# Connector_Exp.net
KiCad netlist of a schematic drawn in Altium Designer
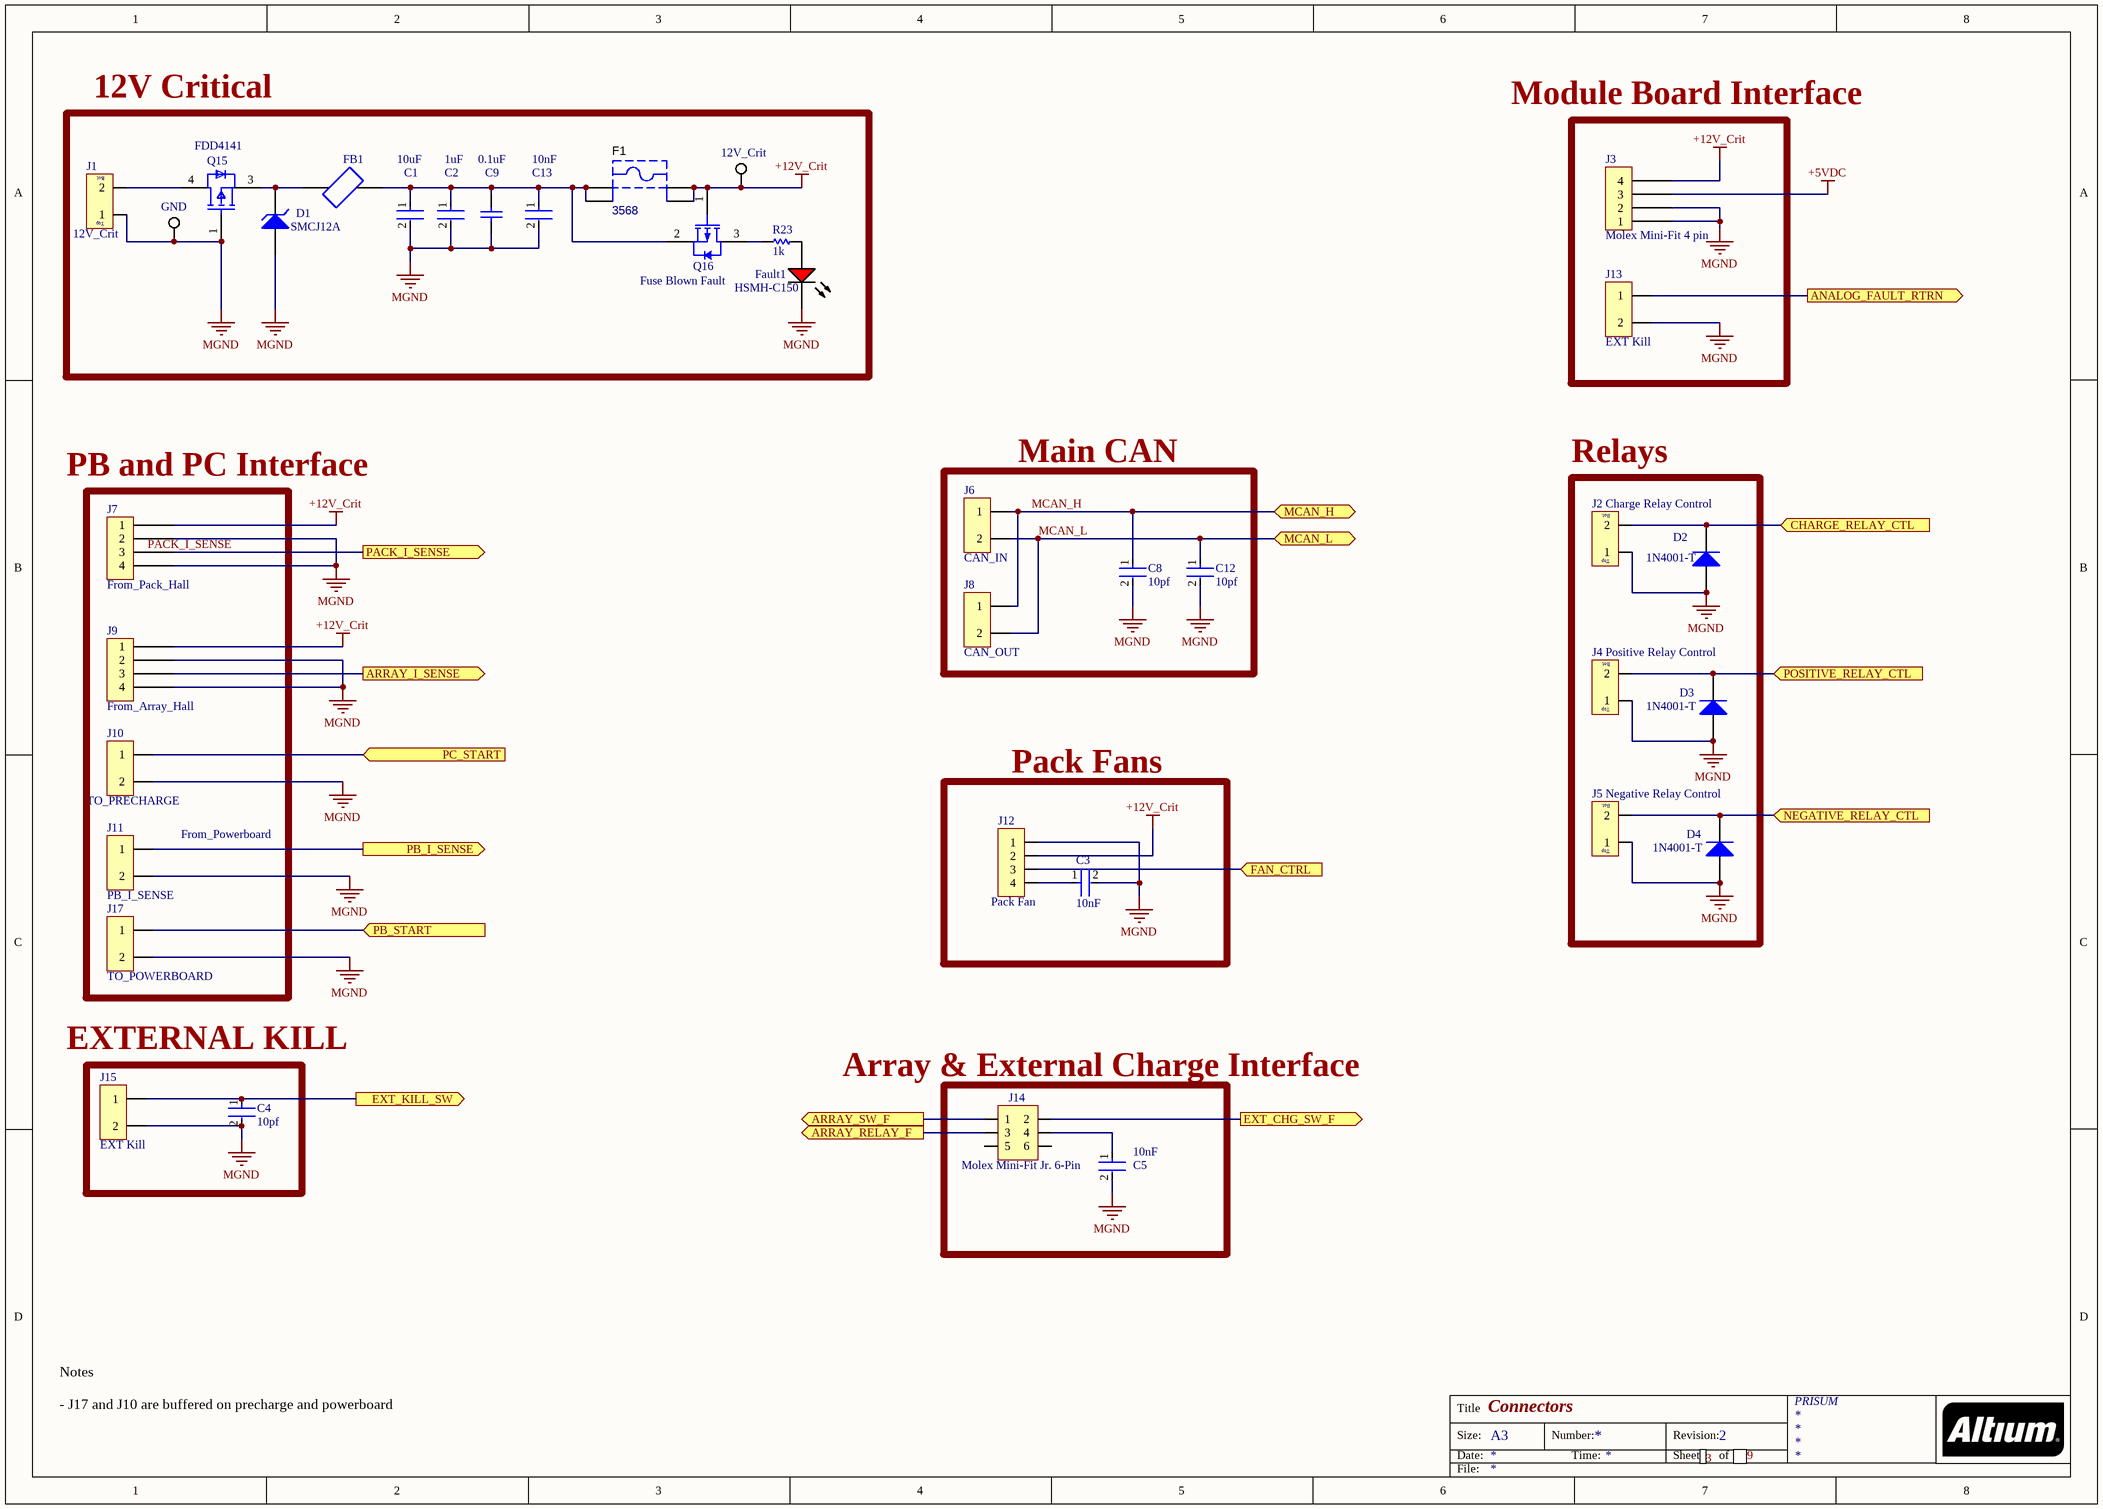
[diagram p0: Connector_Exp.SchDoc]

(export (version "E")
  (design (tool "Eeschema 10.0.6"))
  (components
    (comp (ref "12V_Crit")
      (value "Test Point")
      (footprint "Test Point")
      (libsource (lib "BPS") (part "Test Point"))
    )
    (comp (ref "C1")
      (value "CL31A106MOHNNNE")
      (footprint "FP-CL31-IPC_A")
      (description "Cap Ceramic 10uF 16V X5R ±20% SMD 1206 +85°C Embossed T/R")
      (fields (field (name "CAPACITANCE") "10uF") (field (name "TOLERANCE") "20%"))
      (libsource (lib "Altium Content Vault") (part "b4654b650e69147ec39a6b967a45e02"))
    )
    (comp (ref "C2")
      (value "CL31F105ZOCNNNC")
      (footprint "FP-CL31-IPC_A")
      (description "Cap Ceramic 1uF 16V Y5V -20/+80% SMD 1206 +85°C Embossed T/R")
      (fields (field (name "TOLERANCE") "80%") (field (name "CAPACITANCE") "1uF"))
      (libsource (lib "Altium Content Vault") (part "b4654b650e69147ec39a6b967a45e02"))
    )
    (comp (ref "C3")
      (value "CGA3E2X8R2A103K080AD")
      (footprint "FP-CGA3E-0_3-0_1-IPC_A")
      (description "Cap Ceramic 10nF 100V X8R 10% Pad SMD 0603 +150°C Automotive T/R")
      (fields (field (name "CAPACITANCE") "10nF") (field (name "TOLERANCE") "10%"))
      (libsource (lib "Altium Content Vault") (part "b4654b650e69147ec39a6b967a45e02"))
    )
    (comp (ref "C4")
      (value "10pf")
      (footprint "FP-C0805C-DN-MFG")
      (description "C0805 10 pF C0G 30ppm/°C 2.00% 50 V")
      (fields
        (field (name "TOLERANCE") "0.02")
        (field (name "OCTOPART") "https://octopart.com/c0805c100g5gactu-kemet-20071675")
      )
      (libsource (lib "Altium Content Vault") (part "b4654b650e69147ec39a6b967a45e02"))
    )
    (comp (ref "C5")
      (value "CGA3E2X8R2A103K080AD")
      (footprint "FP-CGA3E-0_3-0_1-IPC_A")
      (description "Cap Ceramic 10nF 100V X8R 10% Pad SMD 0603 +150°C Automotive T/R")
      (fields (field (name "CAPACITANCE") "10nF") (field (name "TOLERANCE") "10%"))
      (libsource (lib "Altium Content Vault") (part "b4654b650e69147ec39a6b967a45e02"))
    )
    (comp (ref "C8")
      (value "10pf")
      (footprint "FP-C0805C-DN-MFG")
      (description "C0805 10 pF C0G 30ppm/°C 2.00% 50 V")
      (fields
        (field (name "TOLERANCE") "0.02")
        (field (name "OCTOPART") "https://octopart.com/c0805c100g5gactu-kemet-20071675")
      )
      (libsource (lib "Altium Content Vault") (part "b4654b650e69147ec39a6b967a45e02"))
    )
    (comp (ref "C9")
      (value "08055C104JAT2A")
      (footprint "CAPC2013X94X50LL20T25")
      (description "Chip Capacitor, 0.1 uF, +/- 5%, 50 V, -55 to 125 degC, 0805 (2012 Metric), RoHS, Tape and Reel")
      (fields
        (field (name "CAPACITANCE") "0.1uF")
        (field (name "TOLERANCE") "5%")
        (field (name "MANUFACTURER") "AVX")
      )
      (libsource (lib "Altium Content Vault") (part "CAP-NP-2"))
    )
    (comp (ref "C12")
      (value "10pf")
      (footprint "FP-C0805C-DN-MFG")
      (description "C0805 10 pF C0G 30ppm/°C 2.00% 50 V")
      (fields
        (field (name "TOLERANCE") "0.02")
        (field (name "OCTOPART") "https://octopart.com/c0805c100g5gactu-kemet-20071675")
      )
      (libsource (lib "Altium Content Vault") (part "b4654b650e69147ec39a6b967a45e02"))
    )
    (comp (ref "C13")
      (value "CGA3E2X8R2A103K080AD")
      (footprint "FP-CGA3E-0_3-0_1-IPC_A")
      (description "Cap Ceramic 10nF 100V X8R 10% Pad SMD 0603 +150°C Automotive T/R")
      (fields (field (name "CAPACITANCE") "10nF") (field (name "TOLERANCE") "10%"))
      (libsource (lib "Altium Content Vault") (part "b4654b650e69147ec39a6b967a45e02"))
    )
    (comp (ref "D1")
      (value "SMCJ12A")
      (footprint "LFUS-DO-214AB-2_V")
      (fields (field (name "MANUFACTURER") "Littelfuse"))
      (libsource (lib "Altium Content Vault") (part "DZEN-AK-2"))
    )
    (comp (ref "D2")
      (value "1N4001-T")
      (footprint "DIOD-DO-41-P-2_V")
      (description "1.0 A Rectifier, 15 pF, 50 V, -65 to 150 degC, 2-Pin DO-41 Plastic, RoHS, Tape and Reel")
      (fields (field (name "MANUFACTURER") "Diodes Inc"))
      (libsource (lib "Altium Content Vault") (part "DIOD-D-A1K2-2"))
    )
    (comp (ref "D3")
      (value "1N4001-T")
      (footprint "DIOD-DO-41-P-2_V")
      (description "1.0 A Rectifier, 15 pF, 50 V, -65 to 150 degC, 2-Pin DO-41 Plastic, RoHS, Tape and Reel")
      (fields (field (name "MANUFACTURER") "Diodes Inc"))
      (libsource (lib "Altium Content Vault") (part "DIOD-D-A1K2-2"))
    )
    (comp (ref "D4")
      (value "1N4001-T")
      (footprint "DIOD-DO-41-P-2_V")
      (description "1.0 A Rectifier, 15 pF, 50 V, -65 to 150 degC, 2-Pin DO-41 Plastic, RoHS, Tape and Reel")
      (fields (field (name "MANUFACTURER") "Diodes Inc"))
      (libsource (lib "Altium Content Vault") (part "DIOD-D-A1K2-2"))
    )
    (comp (ref "F1")
      (value "3568")
      (footprint "KSTN-3568_V")
      (description "Fuse Holder, 20 A, 500 V, -50 to 145 degC, 4-Pin THD, RoHS")
      (fields (field (name "MANUFACTURER") "Keystone"))
      (libsource (lib "Altium Content Vault") (part "FUSE_HOLDER-4"))
    )
    (comp (ref "Fault1")
      (value "HSMH-C150")
      (footprint "AVAG-HSMX-C150_V")
      (description "LED Uni-Color Red, 65 mW, 25 mA, -40 to 85 degC, 2-Pin SMD, RoHS, Tape and Reel")
      (fields (field (name "MANUFACTURER") "Avago"))
      (libsource (lib "Altium Content Vault") (part "LED-RED-AK-2"))
    )
    (comp (ref "FB1")
      (value "HI1206N800R-10")
      (footprint "FB_HI1206N800R-10")
      (description "80 Ohms @ 100MHz 1 Power, Signal Line Ferrite Bead 1206 (3216 Metric) 3A 35mOhm")
      (fields
        (field (name "MF") "Laird-Signal Integrity")
        (field (name "DIGI-KEY_PART_NUMBER") "240-2409-1-ND")
      )
      (libsource (lib "BPS") (part "HI1206N800R-10"))
    )
    (comp (ref "GND")
      (value "Test Point")
      (footprint "Test Point")
      (libsource (lib "BPS") (part "Test Point"))
    )
    (comp (ref "J1")
      (value "12V_Crit")
      (footprint "CONN_2P_MEGAFIT_HORIZONTAL")
      (fields
        (field (name "MANUFACTURER PART NUMBER") "0768250002")
        (field (name "MANUFACTURER") "Molex")
        (field (name "DIGIKEY PART NUMBER") "WM11969-ND")
      )
      (libsource (lib "Connectors (1)") (part "CONN_2P_MEGAFIT_HORIZONTAL"))
    )
    (comp (ref "J2")
      (value "Charge Relay Control")
      (footprint "CONN_2P_MEGAFIT_HORIZONTAL")
      (fields
        (field (name "MANUFACTURER PART NUMBER") "0768250002")
        (field (name "MANUFACTURER") "Molex")
        (field (name "DIGIKEY PART NUMBER") "WM11969-ND")
      )
      (libsource (lib "Connectors (1)") (part "CONN_2P_MEGAFIT_HORIZONTAL"))
    )
    (comp (ref "J3")
      (value "Molex Mini-Fit 4 pin")
      (footprint "Molex Mini-Fit Jr. 4-Pin - no flange")
      (libsource (lib "") (part "Molex Mini-Fit 4 pin_1"))
    )
    (comp (ref "J4")
      (value "Positive Relay Control")
      (footprint "CONN_2P_MEGAFIT_HORIZONTAL")
      (fields
        (field (name "MANUFACTURER PART NUMBER") "0768250002")
        (field (name "MANUFACTURER") "Molex")
        (field (name "DIGIKEY PART NUMBER") "WM11969-ND")
      )
      (libsource (lib "Connectors (1)") (part "CONN_2P_MEGAFIT_HORIZONTAL"))
    )
    (comp (ref "J5")
      (value "Negative Relay Control")
      (footprint "CONN_2P_MEGAFIT_HORIZONTAL")
      (fields
        (field (name "MANUFACTURER PART NUMBER") "0768250002")
        (field (name "MANUFACTURER") "Molex")
        (field (name "DIGIKEY PART NUMBER") "WM11969-ND")
      )
      (libsource (lib "Connectors (1)") (part "CONN_2P_MEGAFIT_HORIZONTAL"))
    )
    (comp (ref "J6")
      (value "CAN_IN")
      (footprint "Mini-Fit Jr. 2")
      (description "Mini-Fit Jr. 2-pin Right Angle")
      (fields
        (field (name "MANUFACTURER") "Molex Inc")
        (field (name "MANUFACTURER PART NUMBER") "0039300020")
      )
      (libsource (lib "BPSHeadNode") (part "Mini-Fit Jr. 2-pin"))
    )
    (comp (ref "J7")
      (value "From_Pack_Hall")
      (footprint "Molex Mini-Fit Jr. 4-Pin - no flange")
      (libsource (lib "BPS") (part "Molex Mini-Fit 4 pin"))
    )
    (comp (ref "J8")
      (value "CAN_OUT")
      (footprint "Mini-Fit Jr. 2")
      (description "Mini-Fit Jr. 2-pin Right Angle")
      (fields
        (field (name "MANUFACTURER") "Molex Inc")
        (field (name "MANUFACTURER PART NUMBER") "0039300020")
      )
      (libsource (lib "BPSHeadNode") (part "Mini-Fit Jr. 2-pin"))
    )
    (comp (ref "J9")
      (value "From_Array_Hall")
      (footprint "Molex Mini-Fit Jr. 4-Pin - no flange")
      (libsource (lib "BPS") (part "Molex Mini-Fit 4 pin"))
    )
    (comp (ref "J10")
      (value "TO_PRECHARGE")
      (footprint "Mini-Fit Jr. 2")
      (description "Mini-Fit Jr. 2-pin Right Angle")
      (fields
        (field (name "MANUFACTURER") "Molex Inc")
        (field (name "MANUFACTURER PART NUMBER") "0039300020")
      )
      (libsource (lib "BPSHeadNode") (part "Mini-Fit Jr. 2-pin"))
    )
    (comp (ref "J11")
      (value "PB_I_SENSE")
      (footprint "Mini-Fit Jr. 2")
      (description "Mini-Fit Jr. 2-pin Right Angle")
      (fields
        (field (name "MANUFACTURER") "Molex Inc")
        (field (name "MANUFACTURER PART NUMBER") "0039300020")
      )
      (libsource (lib "BPSHeadNode") (part "Mini-Fit Jr. 2-pin"))
    )
    (comp (ref "J12")
      (value "Molex Mini-Fit Jr. 4-Pin no flange")
      (footprint "Molex Mini-Fit Jr. 4-Pin - no flange")
      (description "4-Pin Molex Mini-Fit Jr. Header")
      (fields
        (field (name "MANUFACTURER") "Molex")
        (field (name "MANUFACTURER PART NUMBER") "0039301040")
        (field (name "DRAWN BY") "Aaron Mills")
      )
      (libsource (lib "BPSHeadNode") (part "Molex Mini-Fit Jr. 4-Pin"))
    )
    (comp (ref "J13")
      (value "EXT Kill")
      (footprint "Mini-Fit Jr. 2")
      (description "Mini-Fit Jr. 2-pin Right Angle")
      (fields
        (field (name "MANUFACTURER") "Molex Inc")
        (field (name "MANUFACTURER PART NUMBER") "0039300020")
      )
      (libsource (lib "BPSHeadNode") (part "Mini-Fit Jr. 2-pin"))
    )
    (comp (ref "J14")
      (value "Molex Mini-Fit Jr. 6-Pin")
      (footprint "Molex Mini-Fit Jr. 6-Pin")
      (description "6-Pin Molex Mini-Fit Jr. Header  through hole")
      (fields (field (name "MANUFACTURER") "Molex") (field (name "DRAWN BY") "Aaron Mills"))
      (libsource (lib "BPSHeadNode") (part "Molex Mini-Fit Jr. 6-Pin"))
    )
    (comp (ref "J15")
      (value "EXT Kill")
      (footprint "Mini-Fit Jr. 2")
      (description "Mini-Fit Jr. 2-pin Right Angle")
      (fields
        (field (name "MANUFACTURER") "Molex Inc")
        (field (name "MANUFACTURER PART NUMBER") "0039300020")
      )
      (libsource (lib "BPSHeadNode") (part "Mini-Fit Jr. 2-pin"))
    )
    (comp (ref "J17")
      (value "TO_POWERBOARD")
      (footprint "Mini-Fit Jr. 2")
      (description "Mini-Fit Jr. 2-pin Right Angle")
      (fields
        (field (name "MANUFACTURER") "Molex Inc")
        (field (name "MANUFACTURER PART NUMBER") "0039300020")
      )
      (libsource (lib "BPSHeadNode") (part "Mini-Fit Jr. 2-pin"))
    )
    (comp (ref "Q15")
      (value "FDD4141")
      (footprint "FP-369AS-MFG")
      (description "MOSFET P-CH 40V 10.8A DPAK")
      (fields
        (field (name "OCTOPART") "https://octopart.com/fdd4141-on+semiconductor-84325802")
        (field (name "MANUFACTURER") "ON Semiconductor")
      )
      (libsource (lib "Altium Content Vault") (part "ec195c925100855187fe8c06440c3e1"))
    )
    (comp (ref "Q16")
      (value "Fuse Blown Fault")
      (footprint "INTR-SOT-23-3_V")
      (fields (field (name "MANUFACTURER") "International Rectifier"))
      (libsource (lib "Altium Content Vault") (part "PEMOS-GSD-3"))
    )
    (comp (ref "R23")
      (value "RES_1k_1%_0603")
      (footprint "R_0603")
      (fields
        (field (name "MANUFACTURER PART NUMBER") "RC0603FR-071KL")
        (field (name "MANUFACTURER") "Yageo")
        (field (name "DIGIKEY PART NUMBER") "311-1.00KHRCT-ND")
        (field (name "SCHEMATICINFORMATION") "1k")
      )
      (libsource (lib "Resistors") (part "RES_1k_1%_0603"))
    )
  )
  (nets
    (net (code "1") (name "+5VDC") (class "Default")
      (node (ref "J3") (pin "3") (pinfunction "3_3") (pintype "passive"))
    )
    (net (code "2") (name "+12V_Crit") (class "Default")
      (node (ref "12V_Crit") (pin "1") (pinfunction "1_1") (pintype "passive"))
      (node (ref "F1") (pin "3") (pinfunction "3_3") (pintype "passive"))
      (node (ref "F1") (pin "4") (pinfunction "4_4") (pintype "passive"))
      (node (ref "J12") (pin "2") (pinfunction "2_2") (pintype "passive"))
      (node (ref "J3") (pin "4") (pinfunction "4_4") (pintype "passive"))
      (node (ref "J7") (pin "1") (pinfunction "1_1") (pintype "passive"))
      (node (ref "J9") (pin "1") (pinfunction "1_1") (pintype "passive"))
      (node (ref "Q16") (pin "1") (pinfunction "GATE_1") (pintype "passive"))
    )
    (net (code "3") (name "/ANALOG_FAULT_RTRN") (class "Default")
      (node (ref "J13") (pin "1") (pinfunction "1_1") (pintype "passive"))
    )
    (net (code "4") (name "/ARRAY_I_SENSE") (class "Default")
      (node (ref "J9") (pin "3") (pinfunction "3_3") (pintype "passive"))
    )
    (net (code "5") (name "/ARRAY_RELAY_F") (class "Default")
      (node (ref "J14") (pin "3") (pinfunction "3_3") (pintype "passive"))
    )
    (net (code "6") (name "/ARRAY_SW_F") (class "Default")
      (node (ref "J14") (pin "1") (pinfunction "1_1") (pintype "passive"))
    )
    (net (code "7") (name "/CHARGE_RELAY_CTL") (class "Default")
      (node (ref "D2") (pin "2") (pinfunction "K_2") (pintype "passive"))
      (node (ref "J2") (pin "2") (pinfunction "2_2") (pintype "passive"))
    )
    (net (code "8") (name "/EXT_CHG_SW_F") (class "Default")
      (node (ref "J14") (pin "2") (pinfunction "2_2") (pintype "passive"))
    )
    (net (code "9") (name "/EXT_KILL_SW") (class "Default")
      (node (ref "C4") (pin "1") (pinfunction "1_1") (pintype "passive"))
      (node (ref "J15") (pin "1") (pinfunction "1_1") (pintype "passive"))
    )
    (net (code "10") (name "/FAN_CTRL") (class "Default")
      (node (ref "J12") (pin "3") (pinfunction "3_3") (pintype "passive"))
    )
    (net (code "11") (name "/MCAN_H") (class "Default")
      (node (ref "C8") (pin "1") (pinfunction "1_1") (pintype "passive"))
      (node (ref "J6") (pin "1") (pinfunction "1_1") (pintype "passive"))
      (node (ref "J8") (pin "1") (pinfunction "1_1") (pintype "passive"))
    )
    (net (code "12") (name "/MCAN_L") (class "Default")
      (node (ref "C12") (pin "1") (pinfunction "1_1") (pintype "passive"))
      (node (ref "J6") (pin "2") (pinfunction "2_2") (pintype "passive"))
      (node (ref "J8") (pin "2") (pinfunction "2_2") (pintype "passive"))
    )
    (net (code "13") (name "/NEGATIVE_RELAY_CTL") (class "Default")
      (node (ref "D4") (pin "2") (pinfunction "K_2") (pintype "passive"))
      (node (ref "J5") (pin "2") (pinfunction "2_2") (pintype "passive"))
    )
    (net (code "14") (name "/PACK_I_SENSE") (class "Default")
      (node (ref "J7") (pin "3") (pinfunction "3_3") (pintype "passive"))
    )
    (net (code "15") (name "/PB_I_SENSE") (class "Default")
      (node (ref "J11") (pin "1") (pinfunction "1_1") (pintype "passive"))
    )
    (net (code "16") (name "/PB_START") (class "Default")
      (node (ref "J17") (pin "1") (pinfunction "1_1") (pintype "passive"))
    )
    (net (code "17") (name "/PC_START") (class "Default")
      (node (ref "J10") (pin "1") (pinfunction "1_1") (pintype "passive"))
    )
    (net (code "18") (name "/POSITIVE_RELAY_CTL") (class "Default")
      (node (ref "D3") (pin "2") (pinfunction "K_2") (pintype "passive"))
      (node (ref "J4") (pin "2") (pinfunction "2_2") (pintype "passive"))
    )
    (net (code "19") (name "MGND") (class "Default")
      (node (ref "C1") (pin "2") (pinfunction "2_2") (pintype "passive"))
      (node (ref "C12") (pin "2") (pinfunction "2_2") (pintype "passive"))
      (node (ref "C13") (pin "2") (pinfunction "2_2") (pintype "passive"))
      (node (ref "C2") (pin "2") (pinfunction "2_2") (pintype "passive"))
      (node (ref "C3") (pin "2") (pinfunction "2_2") (pintype "passive"))
      (node (ref "C4") (pin "2") (pinfunction "2_2") (pintype "passive"))
      (node (ref "C5") (pin "2") (pinfunction "2_2") (pintype "passive"))
      (node (ref "C8") (pin "2") (pinfunction "2_2") (pintype "passive"))
      (node (ref "C9") (pin "1") (pinfunction "1_1") (pintype "passive"))
      (node (ref "D1") (pin "1") (pinfunction "A_1") (pintype "passive"))
      (node (ref "D2") (pin "1") (pinfunction "A_1") (pintype "passive"))
      (node (ref "D3") (pin "1") (pinfunction "A_1") (pintype "passive"))
      (node (ref "D4") (pin "1") (pinfunction "A_1") (pintype "passive"))
      (node (ref "Fault1") (pin "2") (pinfunction "K_2") (pintype "passive"))
      (node (ref "GND") (pin "1") (pinfunction "1_1") (pintype "passive"))
      (node (ref "J1") (pin "1") (pinfunction "1_1") (pintype "passive"))
      (node (ref "J10") (pin "2") (pinfunction "2_2") (pintype "passive"))
      (node (ref "J11") (pin "2") (pinfunction "2_2") (pintype "passive"))
      (node (ref "J12") (pin "1") (pinfunction "1_1") (pintype "passive"))
      (node (ref "J13") (pin "2") (pinfunction "2_2") (pintype "passive"))
      (node (ref "J15") (pin "2") (pinfunction "2_2") (pintype "passive"))
      (node (ref "J17") (pin "2") (pinfunction "2_2") (pintype "passive"))
      (node (ref "J2") (pin "1") (pinfunction "1_1") (pintype "passive"))
      (node (ref "J3") (pin "1") (pinfunction "1_1") (pintype "passive"))
      (node (ref "J3") (pin "2") (pinfunction "2_2") (pintype "passive"))
      (node (ref "J4") (pin "1") (pinfunction "1_1") (pintype "passive"))
      (node (ref "J5") (pin "1") (pinfunction "1_1") (pintype "passive"))
      (node (ref "J7") (pin "2") (pinfunction "2_2") (pintype "passive"))
      (node (ref "J7") (pin "4") (pinfunction "4_4") (pintype "passive"))
      (node (ref "J9") (pin "2") (pinfunction "2_2") (pintype "passive"))
      (node (ref "J9") (pin "4") (pinfunction "4_4") (pintype "passive"))
      (node (ref "Q15") (pin "1") (pinfunction "G_1") (pintype "passive"))
    )
    (net (code "20") (name "Net-(C3-Pad1)") (class "Default")
      (node (ref "C3") (pin "1") (pinfunction "1_1") (pintype "passive"))
      (node (ref "J12") (pin "4") (pinfunction "4_4") (pintype "passive"))
    )
    (net (code "21") (name "Net-(C5-Pad1)") (class "Default")
      (node (ref "C5") (pin "1") (pinfunction "1_1") (pintype "passive"))
      (node (ref "J14") (pin "4") (pinfunction "4_4") (pintype "passive"))
    )
    (net (code "22") (name "Net-(D1-K)") (class "Default")
      (node (ref "D1") (pin "2") (pinfunction "K_2") (pintype "passive"))
      (node (ref "FB1") (pin "1") (pinfunction "1_1") (pintype "passive"))
      (node (ref "Q15") (pin "3") (pinfunction "S_3") (pintype "passive"))
    )
    (net (code "23") (name "Net-(Fault1-A)") (class "Default")
      (node (ref "Fault1") (pin "1") (pinfunction "A_1") (pintype "passive"))
      (node (ref "R23") (pin "2") (pinfunction "2_2") (pintype "passive"))
    )
    (net (code "24") (name "Net-(Q15-D)") (class "Default")
      (node (ref "J1") (pin "2") (pinfunction "2_2") (pintype "passive"))
      (node (ref "Q15") (pin "4") (pinfunction "D_4") (pintype "passive"))
    )
    (net (code "25") (name "Net-(Q16-DRAIN)") (class "Default")
      (node (ref "Q16") (pin "3") (pinfunction "DRAIN_3") (pintype "passive"))
      (node (ref "R23") (pin "1") (pinfunction "1_1") (pintype "passive"))
    )
    (net (code "26") (name "Net-(Q16-SOURCE)") (class "Default")
      (node (ref "C1") (pin "1") (pinfunction "1_1") (pintype "passive"))
      (node (ref "C13") (pin "1") (pinfunction "1_1") (pintype "passive"))
      (node (ref "C2") (pin "1") (pinfunction "1_1") (pintype "passive"))
      (node (ref "C9") (pin "2") (pinfunction "2_2") (pintype "passive"))
      (node (ref "F1") (pin "1") (pinfunction "1_1") (pintype "passive"))
      (node (ref "F1") (pin "2") (pinfunction "2_2") (pintype "passive"))
      (node (ref "FB1") (pin "2") (pinfunction "2_2") (pintype "passive"))
      (node (ref "Q16") (pin "2") (pinfunction "SOURCE_2") (pintype "passive"))
    )
    (net (code "27") (name "unconnected-(J14-Pad5)") (class "Default")
      (node (ref "J14") (pin "5") (pinfunction "5_5") (pintype "passive"))
    )
    (net (code "28") (name "unconnected-(J14-Pad6)") (class "Default")
      (node (ref "J14") (pin "6") (pinfunction "6_6") (pintype "passive"))
    )
  )
)
